# 02_-STLinkV2_1.net
KiCad netlist of a schematic drawn in Altium Designer
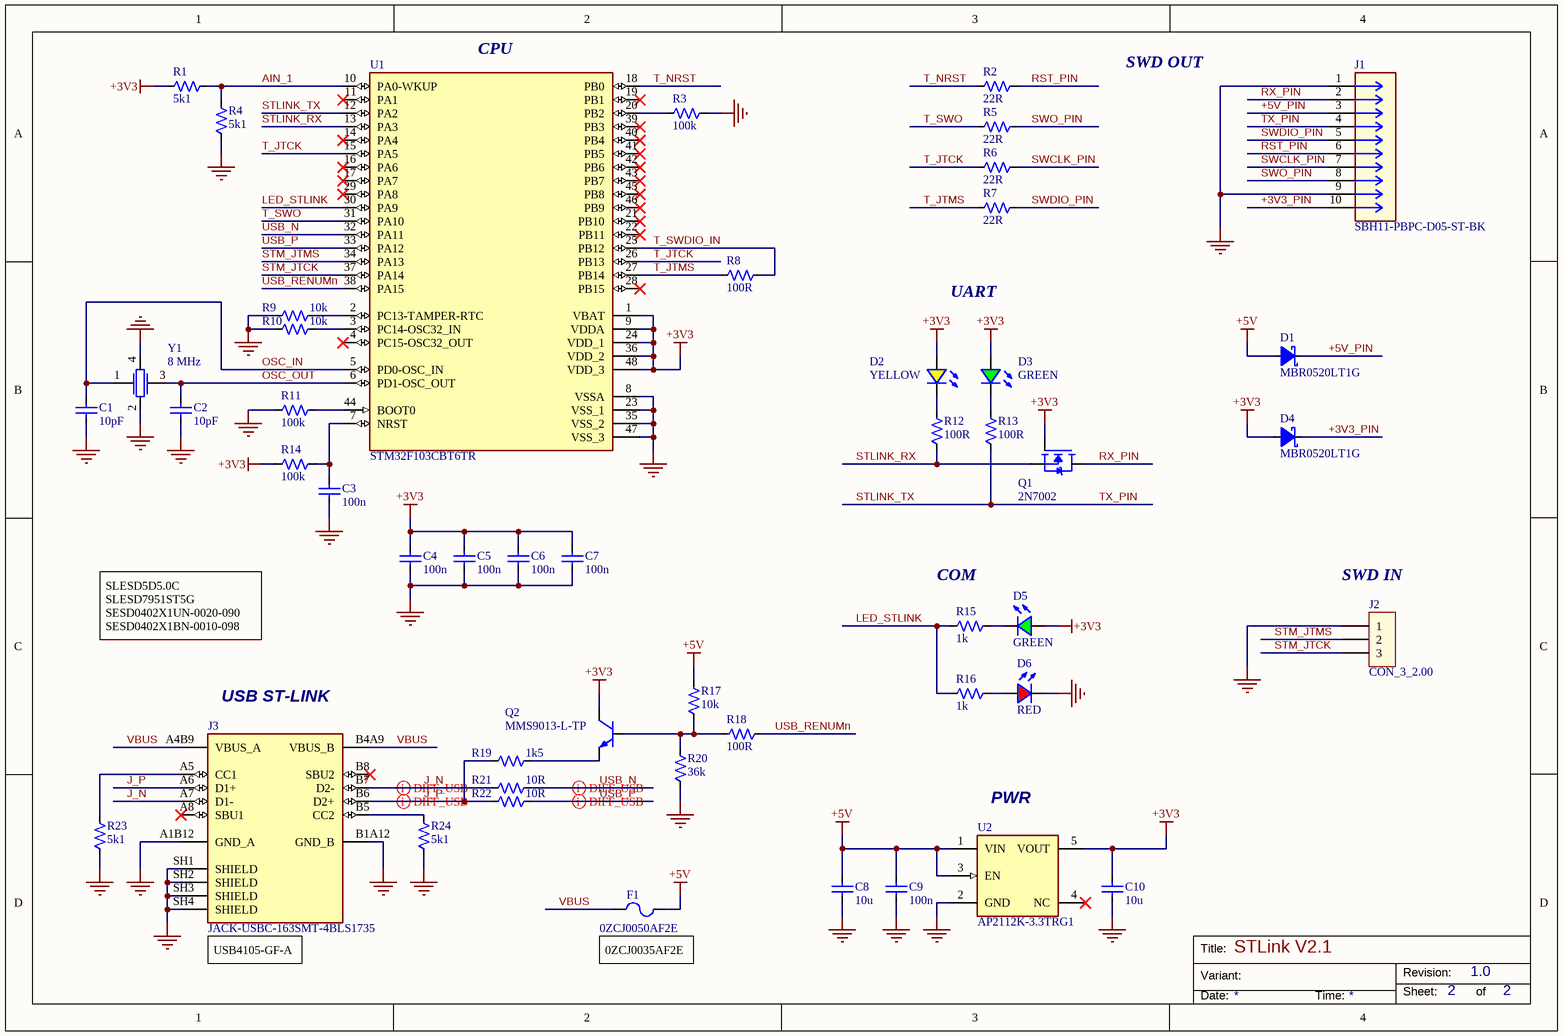
[diagram p0: [02]-STLinkV2_1.SchDoc]

(export (version "E")
  (design (tool "Eeschema 10.0.6"))
  (components
    (comp (ref "C1")
      (value "10pF")
      (footprint "CAPC1005X55N")
      (description "50V 10pF C0G ±5% 0402 Multilayer Ceramic Capacitors MLCC - SMD/SMT ROHS")
      (fields (field (name "TOLERANCE") "5%"))
      (libsource (lib "STLinkV2_1") (part "CAP_GCM1555C1H100JA16D"))
    )
    (comp (ref "C2")
      (value "10pF")
      (footprint "CAPC1005X55N")
      (description "50V 10pF C0G ±5% 0402 Multilayer Ceramic Capacitors MLCC - SMD/SMT ROHS")
      (fields (field (name "TOLERANCE") "5%"))
      (libsource (lib "STLinkV2_1") (part "CAP_GCM1555C1H100JA16D"))
    )
    (comp (ref "C3")
      (value "100n")
      (footprint "CAPC1005X55N")
      (description "50V 100nF X7R ±10% 0402 Multilayer Ceramic Capacitors MLCC - SMD/SMT ROHS")
      (fields (field (name "TOLERANCE") "10%"))
      (libsource (lib "STLinkV2_1") (part "CAP_GCM155R71H104KE02D"))
    )
    (comp (ref "C4")
      (value "100n")
      (footprint "CAPC1005X55N")
      (description "50V 100nF X7R ±10% 0402 Multilayer Ceramic Capacitors MLCC - SMD/SMT ROHS")
      (fields (field (name "TOLERANCE") "10%"))
      (libsource (lib "STLinkV2_1") (part "CAP_GCM155R71H104KE02D"))
    )
    (comp (ref "C5")
      (value "100n")
      (footprint "CAPC1005X55N")
      (description "50V 100nF X7R ±10% 0402 Multilayer Ceramic Capacitors MLCC - SMD/SMT ROHS")
      (fields (field (name "TOLERANCE") "10%"))
      (libsource (lib "STLinkV2_1") (part "CAP_GCM155R71H104KE02D"))
    )
    (comp (ref "C6")
      (value "100n")
      (footprint "CAPC1005X55N")
      (description "50V 100nF X7R ±10% 0402 Multilayer Ceramic Capacitors MLCC - SMD/SMT ROHS")
      (fields (field (name "TOLERANCE") "10%"))
      (libsource (lib "STLinkV2_1") (part "CAP_GCM155R71H104KE02D"))
    )
    (comp (ref "C7")
      (value "100n")
      (footprint "CAPC1005X55N")
      (description "50V 100nF X7R ±10% 0402 Multilayer Ceramic Capacitors MLCC - SMD/SMT ROHS")
      (fields (field (name "TOLERANCE") "10%"))
      (libsource (lib "STLinkV2_1") (part "CAP_GCM155R71H104KE02D"))
    )
    (comp (ref "C8")
      (value "10u")
      (footprint "CAPC0603(1608Metric)L")
      (description "CAP CER 10UF 6.3V X7R 0603")
      (fields (field (name "TOLERANCE") "20%") (field (name "MFG PART NUMBER") "GRM188C81C106MA73D"))
      (libsource (lib "STLinkV2_1") (part "GRM188C81C106MA73D"))
    )
    (comp (ref "C9")
      (value "100n")
      (footprint "CAPC1005X55N")
      (description "50V 100nF X7R ±10% 0402 Multilayer Ceramic Capacitors MLCC - SMD/SMT ROHS")
      (fields (field (name "TOLERANCE") "10%"))
      (libsource (lib "STLinkV2_1") (part "CAP_GCM155R71H104KE02D"))
    )
    (comp (ref "C10")
      (value "10u")
      (footprint "CAPC0603(1608Metric)L")
      (description "CAP CER 10UF 6.3V X7R 0603")
      (fields (field (name "TOLERANCE") "20%") (field (name "MFG PART NUMBER") "GRM188C81C106MA73D"))
      (libsource (lib "STLinkV2_1") (part "GRM188C81C106MA73D"))
    )
    (comp (ref "D1")
      (value "MBR0520LT1G")
      (footprint "SOD3716X135N")
      (description "Diode, Schottky Barrier, Vr 20V, If 0.5A, Pkg SOD-123, Vf 0.385V, Tj +125DEGC, Cs 5.5A")
      (libsource (lib "STLinkV2_1") (part "MBR0520LT1G"))
    )
    (comp (ref "D2")
      (value "YELLOW")
      (footprint "WL-SMCW_0603_150060xx75003")
      (description "Led, Yellow, 550Mcd, 595Nm Rohs Compliant: Yes")
      (libsource (lib "STLinkV2_1") (part "150060YS75003"))
    )
    (comp (ref "D3")
      (value "GREEN")
      (footprint "WL-SMCW_0603_150060xx75003")
      (description "Led, Bright Green, 100Mcd, 572Nm Rohs Compliant: Yes")
      (libsource (lib "STLinkV2_1") (part "150060VS75003"))
    )
    (comp (ref "D4")
      (value "MBR0520LT1G")
      (footprint "SOD3716X135N")
      (description "Diode, Schottky Barrier, Vr 20V, If 0.5A, Pkg SOD-123, Vf 0.385V, Tj +125DEGC, Cs 5.5A")
      (libsource (lib "STLinkV2_1") (part "MBR0520LT1G"))
    )
    (comp (ref "D5")
      (value "GREEN")
      (footprint "WL-SMCW_0603_150060xx75003")
      (description "Led, Bright Green, 100Mcd, 572Nm Rohs Compliant: Yes")
      (libsource (lib "STLinkV2_1") (part "150060VS75003"))
    )
    (comp (ref "D6")
      (value "RED")
      (description "SMT Mono-Color Chip LED Waterclear Advance WL-SMCW_0603_ADVANCE")
      (libsource (lib "STLinkV2_1") (part "150060RS75003"))
    )
    (comp (ref "F1")
      (value "0ZCJ0050AF2E")
      (footprint "0ZCJ_BEL")
      (description "Resettable Fuse, PPTC, 1206 (3216 Metric), 0ZCJ Series, 24 VDC, 500 mA, 1 A, 0.1 s")
      (libsource (lib "STLinkV2_1") (part "0ZCJ0050AF2E"))
    )
    (comp (ref "J1")
      (value "SBH11-PBPC-D05-ST-BK")
      (footprint "SULLINS_SBH11-PBPC-D05-ST-BK-H")
      (description "Conn Shrouded Header (4 Sides) HDR 10 POS 2.54mm Solder ST Top Entry Thru-Hole")
      (libsource (lib "STLinkV2_1") (part "SBH11-PBPC-D05-ST-BK"))
    )
    (comp (ref "J2")
      (value "CON_3_2.00")
      (footprint "Pin3")
      (libsource (lib "STLinkV2_1") (part "CON_3_2.00"))
    )
    (comp (ref "J3")
      (value "JACK-USBC-163SMT-4BLS1735")
      (footprint "JACK-USBC-163SMT-4BLS1735")
      (description "Usb Type C Jack IPX7 SMT")
      (libsource (lib "STLinkV2_1") (part "JACK-USBC-163SMT-4BLS1735"))
    )
    (comp (ref "Q1")
      (value "2N7002")
      (footprint "SOT23-3")
      (description "MOSFET N-CH 60V 300MA SOT23-3 N-Channel 60 V 300mA (Ta) 500mW (Ta) Surface Mount PG-SOT23")
      (libsource (lib "STLinkV2_1") (part "2N7002H6327XTSA2"))
    )
    (comp (ref "Q2")
      (value "MMS9013-L-TP")
      (footprint "SOT23-3")
      (description "Small Signal Bipolar Transistor, 0.5A I(C), 25V V(BR)CEO, 1-Element, NPN, Silicon")
      (libsource (lib "STLinkV2_1") (part "MMS9013-L-TP"))
    )
    (comp (ref "R1")
      (value "5k1")
      (footprint "RESC1005X37N")
      (description "Res Thick Film 0402 5.1K Ohm 1% 0.063W(1/16W) ±100ppm/°C Pad SMD T/R Automotive AEC-Q200")
      (fields (field (name "TOLERANCE") "1%"))
      (libsource (lib "STLinkV2_1") (part "RES_AC0402FR-135K1L"))
    )
    (comp (ref "R2")
      (value "22R")
      (footprint "RESC1005X37N")
      (description "125mW Thick Film Resistors ±100ppm/℃ ±1% 22Ω 0402 Chip Resistor - Surface Mount ROHS")
      (fields (field (name "TOLERANCE") "1%"))
      (libsource (lib "STLinkV2_1") (part "RES_AC0402FR-7W22RL"))
    )
    (comp (ref "R3")
      (value "100k")
      (footprint "RESC1005X37N")
      (description "Res Thick Film 0402 100K Ohm 1% 0.125W(1/8W) ±100ppm/°C Pad SMD T/R Automotive AEC-Q200")
      (fields (field (name "TOLERANCE") "1%"))
      (libsource (lib "STLinkV2_1") (part "RES_AC0402FR-7W100KL"))
    )
    (comp (ref "R4")
      (value "5k1")
      (footprint "RESC1005X37N")
      (description "Res Thick Film 0402 5.1K Ohm 1% 0.063W(1/16W) ±100ppm/°C Pad SMD T/R Automotive AEC-Q200")
      (fields (field (name "TOLERANCE") "1%"))
      (libsource (lib "STLinkV2_1") (part "RES_AC0402FR-135K1L"))
    )
    (comp (ref "R5")
      (value "22R")
      (footprint "RESC1005X37N")
      (description "125mW Thick Film Resistors ±100ppm/℃ ±1% 22Ω 0402 Chip Resistor - Surface Mount ROHS")
      (fields (field (name "TOLERANCE") "1%"))
      (libsource (lib "STLinkV2_1") (part "RES_AC0402FR-7W22RL"))
    )
    (comp (ref "R6")
      (value "22R")
      (footprint "RESC1005X37N")
      (description "125mW Thick Film Resistors ±100ppm/℃ ±1% 22Ω 0402 Chip Resistor - Surface Mount ROHS")
      (fields (field (name "TOLERANCE") "1%"))
      (libsource (lib "STLinkV2_1") (part "RES_AC0402FR-7W22RL"))
    )
    (comp (ref "R7")
      (value "22R")
      (footprint "RESC1005X37N")
      (description "125mW Thick Film Resistors ±100ppm/℃ ±1% 22Ω 0402 Chip Resistor - Surface Mount ROHS")
      (fields (field (name "TOLERANCE") "1%"))
      (libsource (lib "STLinkV2_1") (part "RES_AC0402FR-7W22RL"))
    )
    (comp (ref "R8")
      (value "100R")
      (footprint "RESC1005X37N")
      (description "Res Thick Film 0402 100 Ohm 1% 0.125W(1/8W) ±100ppm/C Pad SMD T/R Automotive AEC-Q200")
      (fields (field (name "TOLERANCE") "1%"))
      (libsource (lib "STLinkV2_1") (part "RES_AC0402FR-7W100RL"))
    )
    (comp (ref "R9")
      (value "10k")
      (footprint "RESC1005X37N")
      (description "Res Thick Film 0402 10K Ohm 1% 0.125W(1/8W) ±100ppm/C Pad SMD Automotive T/R")
      (fields (field (name "TOLERANCE") "1%"))
      (libsource (lib "STLinkV2_1") (part "RES_AC0402FR-7W10KL"))
    )
    (comp (ref "R10")
      (value "10k")
      (footprint "RESC1005X37N")
      (description "Res Thick Film 0402 10K Ohm 1% 0.125W(1/8W) ±100ppm/C Pad SMD Automotive T/R")
      (fields (field (name "TOLERANCE") "1%"))
      (libsource (lib "STLinkV2_1") (part "RES_AC0402FR-7W10KL"))
    )
    (comp (ref "R11")
      (value "100k")
      (footprint "RESC1005X37N")
      (description "Res Thick Film 0402 100K Ohm 1% 0.125W(1/8W) ±100ppm/°C Pad SMD T/R Automotive AEC-Q200")
      (fields (field (name "TOLERANCE") "1%"))
      (libsource (lib "STLinkV2_1") (part "RES_AC0402FR-7W100KL"))
    )
    (comp (ref "R12")
      (value "100R")
      (footprint "RESC1005X37N")
      (description "Res Thick Film 0402 100 Ohm 1% 0.125W(1/8W) ±100ppm/C Pad SMD T/R Automotive AEC-Q200")
      (fields (field (name "TOLERANCE") "1%"))
      (libsource (lib "STLinkV2_1") (part "RES_AC0402FR-7W100RL"))
    )
    (comp (ref "R13")
      (value "100R")
      (footprint "RESC1005X37N")
      (description "Res Thick Film 0402 100 Ohm 1% 0.125W(1/8W) ±100ppm/C Pad SMD T/R Automotive AEC-Q200")
      (fields (field (name "TOLERANCE") "1%"))
      (libsource (lib "STLinkV2_1") (part "RES_AC0402FR-7W100RL"))
    )
    (comp (ref "R14")
      (value "100k")
      (footprint "RESC1005X37N")
      (description "Res Thick Film 0402 100K Ohm 1% 0.125W(1/8W) ±100ppm/°C Pad SMD T/R Automotive AEC-Q200")
      (fields (field (name "TOLERANCE") "1%"))
      (libsource (lib "STLinkV2_1") (part "RES_AC0402FR-7W100KL"))
    )
    (comp (ref "R15")
      (value "1k")
      (footprint "RESC1005X37N")
      (description "Res Thick Film 0402 1K Ohm 1% 0.125W(1/8W) ±100ppm/C Pad SMD Automotive T/R")
      (fields (field (name "TOLERANCE") "1%"))
      (libsource (lib "STLinkV2_1") (part "RES_AC0402FR-7W1KL"))
    )
    (comp (ref "R16")
      (value "1k")
      (footprint "RESC1005X37N")
      (description "Res Thick Film 0402 1K Ohm 1% 0.125W(1/8W) ±100ppm/C Pad SMD Automotive T/R")
      (fields (field (name "TOLERANCE") "1%"))
      (libsource (lib "STLinkV2_1") (part "RES_AC0402FR-7W1KL"))
    )
    (comp (ref "R17")
      (value "10k")
      (footprint "RESC1005X37N")
      (description "Res Thick Film 0402 10K Ohm 1% 0.125W(1/8W) ±100ppm/C Pad SMD Automotive T/R")
      (fields (field (name "TOLERANCE") "1%"))
      (libsource (lib "STLinkV2_1") (part "RES_AC0402FR-7W10KL"))
    )
    (comp (ref "R18")
      (value "100R")
      (footprint "RESC1005X37N")
      (description "Res Thick Film 0402 100 Ohm 1% 0.125W(1/8W) ±100ppm/C Pad SMD T/R Automotive AEC-Q200")
      (fields (field (name "TOLERANCE") "1%"))
      (libsource (lib "STLinkV2_1") (part "RES_AC0402FR-7W100RL"))
    )
    (comp (ref "R19")
      (value "1k5")
      (footprint "RESC1005X37N")
      (fields (field (name "TOLERANCE") "1%"))
      (libsource (lib "STLinkV2_1") (part "RES_AC0402FR-7W1K5L"))
    )
    (comp (ref "R20")
      (value "36k")
      (footprint "RESC1005X37N")
      (description "Chip Resistor Automotive Grade Thick Film 0402 36kOhm 1% Paper T/R")
      (fields (field (name "TOLERANCE") "1%"))
      (libsource (lib "STLinkV2_1") (part "RES_AC0402FR-7W36KL"))
    )
    (comp (ref "R21")
      (value "10R")
      (footprint "RESC1005X37N")
      (description "Res Thick Film 0402 10 Ohm 1% 0.125W(1/8W) ±100ppm/C Pad SMD T/R Automotive AEC-Q200")
      (fields (field (name "TOLERANCE") "1%"))
      (libsource (lib "STLinkV2_1") (part "RES_AC0402FR-7W10RL"))
    )
    (comp (ref "R22")
      (value "10R")
      (footprint "RESC1005X37N")
      (description "Res Thick Film 0402 10 Ohm 1% 0.125W(1/8W) ±100ppm/C Pad SMD T/R Automotive AEC-Q200")
      (fields (field (name "TOLERANCE") "1%"))
      (libsource (lib "STLinkV2_1") (part "RES_AC0402FR-7W10RL"))
    )
    (comp (ref "R23")
      (value "5k1")
      (footprint "RESC1005X37N")
      (description "Res Thick Film 0402 5.1K Ohm 1% 0.063W(1/16W) ±100ppm/°C Pad SMD T/R Automotive AEC-Q200")
      (fields (field (name "TOLERANCE") "1%"))
      (libsource (lib "STLinkV2_1") (part "RES_AC0402FR-135K1L"))
    )
    (comp (ref "R24")
      (value "5k1")
      (footprint "RESC1005X37N")
      (description "Res Thick Film 0402 5.1K Ohm 1% 0.063W(1/16W) ±100ppm/°C Pad SMD T/R Automotive AEC-Q200")
      (fields (field (name "TOLERANCE") "1%"))
      (libsource (lib "STLinkV2_1") (part "RES_AC0402FR-135K1L"))
    )
    (comp (ref "U1")
      (value "STM32F103CBT6TR")
      (footprint "QFP50P900X900X160-48N")
      (description "MCU 32-bit STM32F1 ARM Cortex M3 RISC 128KB Flash 2.5V/3.3V 48-Pin LQFP T/R")
      (libsource (lib "STLinkV2_1") (part "STM32F103CBT6TR"))
    )
    (comp (ref "U2")
      (value "AP2112K-3.3TRG1")
      (footprint "SOT95P285X140-5N")
      (description "AP2112 Series 0.6 A 3.3 V Fixed Output SMT LDO Linear Regulator - SOT23-5")
      (libsource (lib "STLinkV2_1") (part "AP2112K-3.3TRG1"))
    )
    (comp (ref "Y1")
      (value "8 MHz")
      (footprint "XTAL_C3E-8.000-8-1015-R")
      (description "CRYSTAL 8.0000MHZ 10PF SMD")
      (fields (field (name "MFG") "ECS Inc.") (field (name "MFG PART NUMBER") "ECS-80-10-33-CKM-TR3"))
      (libsource (lib "STLinkV2_1") (part "Y_ECS-80-10-33-CKM-TR3"))
    )
  )
  (nets
    (net (code "1") (name "+3V3") (class "Default")
      (node (ref "C10") (pin "2") (pinfunction "2_2") (pintype "passive"))
      (node (ref "C4") (pin "1") (pinfunction "1_1") (pintype "passive"))
      (node (ref "C5") (pin "1") (pinfunction "1_1") (pintype "passive"))
      (node (ref "C6") (pin "1") (pinfunction "1_1") (pintype "passive"))
      (node (ref "C7") (pin "1") (pinfunction "1_1") (pintype "passive"))
      (node (ref "D2") (pin "1") (pinfunction "POS_1") (pintype "passive"))
      (node (ref "D3") (pin "1") (pinfunction "POS_1") (pintype "passive"))
      (node (ref "D4") (pin "1") (pinfunction "A_1") (pintype "passive"))
      (node (ref "D5") (pin "1") (pinfunction "POS_1") (pintype "passive"))
      (node (ref "Q1") (pin "1") (pinfunction "G_1") (pintype "passive"))
      (node (ref "Q2") (pin "3") (pinfunction "C_3") (pintype "passive"))
      (node (ref "R1") (pin "2") (pinfunction "2_2") (pintype "passive"))
      (node (ref "R14") (pin "2") (pinfunction "2_2") (pintype "passive"))
      (node (ref "U1") (pin "1") (pinfunction "VBAT_1") (pintype "power_in"))
      (node (ref "U1") (pin "24") (pinfunction "VDD_1_24") (pintype "power_in"))
      (node (ref "U1") (pin "36") (pinfunction "VDD_2_36") (pintype "power_in"))
      (node (ref "U1") (pin "48") (pinfunction "VDD_3_48") (pintype "power_in"))
      (node (ref "U1") (pin "9") (pinfunction "VDDA_9") (pintype "power_in"))
      (node (ref "U2") (pin "5") (pinfunction "VOUT_5") (pintype "power_in"))
    )
    (net (code "2") (name "+5V") (class "Default")
      (node (ref "C8") (pin "2") (pinfunction "2_2") (pintype "passive"))
      (node (ref "C9") (pin "1") (pinfunction "1_1") (pintype "passive"))
      (node (ref "D1") (pin "1") (pinfunction "A_1") (pintype "passive"))
      (node (ref "F1") (pin "2") (pinfunction "2_2") (pintype "passive"))
      (node (ref "R17") (pin "1") (pinfunction "1_1") (pintype "passive"))
      (node (ref "U2") (pin "1") (pinfunction "VIN_1") (pintype "power_in"))
      (node (ref "U2") (pin "3") (pinfunction "EN_3") (pintype "input"))
    )
    (net (code "3") (name "/+3V3_PIN") (class "Default")
      (node (ref "D4") (pin "2") (pinfunction "K_2") (pintype "passive"))
      (node (ref "J1") (pin "10") (pinfunction "10_10") (pintype "passive"))
    )
    (net (code "4") (name "/+5V_PIN") (class "Default")
      (node (ref "D1") (pin "2") (pinfunction "K_2") (pintype "passive"))
      (node (ref "J1") (pin "3") (pinfunction "3_3") (pintype "passive"))
    )
    (net (code "5") (name "/AIN_1") (class "Default")
      (node (ref "R1") (pin "1") (pinfunction "1_1") (pintype "passive"))
      (node (ref "R4") (pin "1") (pinfunction "1_1") (pintype "passive"))
      (node (ref "U1") (pin "10") (pinfunction "PA0-WKUP_10") (pintype "bidirectional"))
    )
    (net (code "6") (name "/J_N") (class "Default")
      (node (ref "J3") (pin "A7") (pinfunction "D1-_A7") (pintype "bidirectional"))
      (node (ref "J3") (pin "B7") (pinfunction "D2-_B7") (pintype "bidirectional"))
      (node (ref "R21") (pin "2") (pinfunction "2_2") (pintype "passive"))
    )
    (net (code "7") (name "/J_P") (class "Default")
      (node (ref "J3") (pin "A6") (pinfunction "D1+_A6") (pintype "bidirectional"))
      (node (ref "J3") (pin "B6") (pinfunction "D2+_B6") (pintype "bidirectional"))
      (node (ref "R19") (pin "2") (pinfunction "2_2") (pintype "passive"))
      (node (ref "R22") (pin "2") (pinfunction "2_2") (pintype "passive"))
    )
    (net (code "8") (name "/LED_STLINK") (class "Default")
      (node (ref "R15") (pin "2") (pinfunction "2_2") (pintype "passive"))
      (node (ref "R16") (pin "2") (pinfunction "2_2") (pintype "passive"))
      (node (ref "U1") (pin "30") (pinfunction "PA9_30") (pintype "bidirectional"))
    )
    (net (code "9") (name "/OSC_IN") (class "Default")
      (node (ref "C1") (pin "2") (pinfunction "2_2") (pintype "passive"))
      (node (ref "U1") (pin "5") (pinfunction "PD0-OSC_IN_5") (pintype "bidirectional"))
      (node (ref "Y1") (pin "1") (pinfunction "1_1") (pintype "passive"))
    )
    (net (code "10") (name "/OSC_OUT") (class "Default")
      (node (ref "C2") (pin "2") (pinfunction "2_2") (pintype "passive"))
      (node (ref "U1") (pin "6") (pinfunction "PD1-OSC_OUT_6") (pintype "bidirectional"))
      (node (ref "Y1") (pin "3") (pinfunction "2_3") (pintype "passive"))
    )
    (net (code "11") (name "/RST_PIN") (class "Default")
      (node (ref "J1") (pin "6") (pinfunction "6_6") (pintype "passive"))
      (node (ref "R2") (pin "1") (pinfunction "1_1") (pintype "passive"))
    )
    (net (code "12") (name "/RX_PIN") (class "Default")
      (node (ref "J1") (pin "2") (pinfunction "2_2") (pintype "passive"))
      (node (ref "Q1") (pin "3") (pinfunction "D_3") (pintype "passive"))
    )
    (net (code "13") (name "/STLINK_RX") (class "Default")
      (node (ref "Q1") (pin "2") (pinfunction "S_2") (pintype "passive"))
      (node (ref "R12") (pin "2") (pinfunction "2_2") (pintype "passive"))
      (node (ref "U1") (pin "13") (pinfunction "PA3_13") (pintype "bidirectional"))
    )
    (net (code "14") (name "/STLINK_TX") (class "Default")
      (node (ref "J1") (pin "4") (pinfunction "4_4") (pintype "passive"))
      (node (ref "R13") (pin "2") (pinfunction "2_2") (pintype "passive"))
      (node (ref "U1") (pin "12") (pinfunction "PA2_12") (pintype "bidirectional"))
    )
    (net (code "15") (name "/STM_JTCK") (class "Default")
      (node (ref "J2") (pin "3") (pinfunction "3_3") (pintype "passive"))
      (node (ref "U1") (pin "37") (pinfunction "PA14_37") (pintype "bidirectional"))
    )
    (net (code "16") (name "/STM_JTMS") (class "Default")
      (node (ref "J2") (pin "2") (pinfunction "2_2") (pintype "passive"))
      (node (ref "U1") (pin "34") (pinfunction "PA13_34") (pintype "bidirectional"))
    )
    (net (code "17") (name "/SWCLK_PIN") (class "Default")
      (node (ref "J1") (pin "7") (pinfunction "7_7") (pintype "passive"))
      (node (ref "R6") (pin "1") (pinfunction "1_1") (pintype "passive"))
    )
    (net (code "18") (name "/SWDIO_PIN") (class "Default")
      (node (ref "J1") (pin "5") (pinfunction "5_5") (pintype "passive"))
      (node (ref "R7") (pin "1") (pinfunction "1_1") (pintype "passive"))
    )
    (net (code "19") (name "/SWO_PIN") (class "Default")
      (node (ref "J1") (pin "8") (pinfunction "8_8") (pintype "passive"))
      (node (ref "R5") (pin "1") (pinfunction "1_1") (pintype "passive"))
    )
    (net (code "20") (name "/T_JTCK") (class "Default")
      (node (ref "R6") (pin "2") (pinfunction "2_2") (pintype "passive"))
      (node (ref "U1") (pin "15") (pinfunction "PA5_15") (pintype "bidirectional"))
      (node (ref "U1") (pin "26") (pinfunction "PB13_26") (pintype "bidirectional"))
    )
    (net (code "21") (name "/T_JTMS") (class "Default")
      (node (ref "R7") (pin "2") (pinfunction "2_2") (pintype "passive"))
      (node (ref "R8") (pin "2") (pinfunction "2_2") (pintype "passive"))
      (node (ref "U1") (pin "27") (pinfunction "PB14_27") (pintype "bidirectional"))
    )
    (net (code "22") (name "/T_NRST") (class "Default")
      (node (ref "R2") (pin "2") (pinfunction "2_2") (pintype "passive"))
      (node (ref "U1") (pin "18") (pinfunction "PB0_18") (pintype "bidirectional"))
    )
    (net (code "23") (name "/T_SWDIO_IN") (class "Default")
      (node (ref "R8") (pin "1") (pinfunction "1_1") (pintype "passive"))
      (node (ref "U1") (pin "25") (pinfunction "PB12_25") (pintype "bidirectional"))
    )
    (net (code "24") (name "/T_SWO") (class "Default")
      (node (ref "R5") (pin "2") (pinfunction "2_2") (pintype "passive"))
      (node (ref "U1") (pin "31") (pinfunction "PA10_31") (pintype "bidirectional"))
    )
    (net (code "25") (name "/USB_N") (class "Default")
      (node (ref "R21") (pin "1") (pinfunction "1_1") (pintype "passive"))
      (node (ref "U1") (pin "32") (pinfunction "PA11_32") (pintype "bidirectional"))
    )
    (net (code "26") (name "/USB_P") (class "Default")
      (node (ref "R22") (pin "1") (pinfunction "1_1") (pintype "passive"))
      (node (ref "U1") (pin "33") (pinfunction "PA12_33") (pintype "bidirectional"))
    )
    (net (code "27") (name "/USB_RENUMn") (class "Default")
      (node (ref "R18") (pin "2") (pinfunction "2_2") (pintype "passive"))
      (node (ref "U1") (pin "38") (pinfunction "PA15_38") (pintype "bidirectional"))
    )
    (net (code "28") (name "/VBUS") (class "Default")
      (node (ref "F1") (pin "1") (pinfunction "1_1") (pintype "passive"))
      (node (ref "J3") (pin "A4B9") (pinfunction "VBUS_A_A4B9") (pintype "power_in"))
      (node (ref "J3") (pin "B4A9") (pinfunction "VBUS_B_B4A9") (pintype "power_in"))
    )
    (net (code "29") (name "GND") (class "Default")
      (node (ref "C1") (pin "1") (pinfunction "1_1") (pintype "passive"))
      (node (ref "C10") (pin "1") (pinfunction "1_1") (pintype "passive"))
      (node (ref "C2") (pin "1") (pinfunction "1_1") (pintype "passive"))
      (node (ref "C3") (pin "2") (pinfunction "2_2") (pintype "passive"))
      (node (ref "C4") (pin "2") (pinfunction "2_2") (pintype "passive"))
      (node (ref "C5") (pin "2") (pinfunction "2_2") (pintype "passive"))
      (node (ref "C6") (pin "2") (pinfunction "2_2") (pintype "passive"))
      (node (ref "C7") (pin "2") (pinfunction "2_2") (pintype "passive"))
      (node (ref "C8") (pin "1") (pinfunction "1_1") (pintype "passive"))
      (node (ref "C9") (pin "2") (pinfunction "2_2") (pintype "passive"))
      (node (ref "D6") (pin "2") (pinfunction "NEG_2") (pintype "passive"))
      (node (ref "J1") (pin "1") (pinfunction "1_1") (pintype "passive"))
      (node (ref "J1") (pin "9") (pinfunction "9_9") (pintype "passive"))
      (node (ref "J2") (pin "1") (pinfunction "1_1") (pintype "passive"))
      (node (ref "J3") (pin "A1B12") (pinfunction "GND_A_A1B12") (pintype "power_in"))
      (node (ref "J3") (pin "B1A12") (pinfunction "GND_B_B1A12") (pintype "power_in"))
      (node (ref "J3") (pin "SH1") (pinfunction "SHIELD_SH1") (pintype "passive"))
      (node (ref "J3") (pin "SH2") (pinfunction "SHIELD_SH2") (pintype "passive"))
      (node (ref "J3") (pin "SH3") (pinfunction "SHIELD_SH3") (pintype "passive"))
      (node (ref "J3") (pin "SH4") (pinfunction "SHIELD_SH4") (pintype "passive"))
      (node (ref "R10") (pin "2") (pinfunction "2_2") (pintype "passive"))
      (node (ref "R11") (pin "2") (pinfunction "2_2") (pintype "passive"))
      (node (ref "R20") (pin "2") (pinfunction "2_2") (pintype "passive"))
      (node (ref "R23") (pin "2") (pinfunction "2_2") (pintype "passive"))
      (node (ref "R24") (pin "2") (pinfunction "2_2") (pintype "passive"))
      (node (ref "R3") (pin "1") (pinfunction "1_1") (pintype "passive"))
      (node (ref "R4") (pin "2") (pinfunction "2_2") (pintype "passive"))
      (node (ref "R9") (pin "2") (pinfunction "2_2") (pintype "passive"))
      (node (ref "U1") (pin "23") (pinfunction "VSS_1_23") (pintype "power_in"))
      (node (ref "U1") (pin "35") (pinfunction "VSS_2_35") (pintype "power_in"))
      (node (ref "U1") (pin "47") (pinfunction "VSS_3_47") (pintype "power_in"))
      (node (ref "U1") (pin "8") (pinfunction "VSSA_8") (pintype "power_in"))
      (node (ref "U2") (pin "2") (pinfunction "GND_2") (pintype "power_in"))
      (node (ref "Y1") (pin "2") (pinfunction "GND_2") (pintype "power_in"))
      (node (ref "Y1") (pin "4") (pinfunction "GND_4") (pintype "power_in"))
    )
    (net (code "30") (name "Net-(D2-NEG)") (class "Default")
      (node (ref "D2") (pin "2") (pinfunction "NEG_2") (pintype "passive"))
      (node (ref "R12") (pin "1") (pinfunction "1_1") (pintype "passive"))
    )
    (net (code "31") (name "Net-(D3-NEG)") (class "Default")
      (node (ref "D3") (pin "2") (pinfunction "NEG_2") (pintype "passive"))
      (node (ref "R13") (pin "1") (pinfunction "1_1") (pintype "passive"))
    )
    (net (code "32") (name "Net-(D5-NEG)") (class "Default")
      (node (ref "D5") (pin "2") (pinfunction "NEG_2") (pintype "passive"))
      (node (ref "R15") (pin "1") (pinfunction "1_1") (pintype "passive"))
    )
    (net (code "33") (name "Net-(D6-POS)") (class "Default")
      (node (ref "D6") (pin "1") (pinfunction "POS_1") (pintype "passive"))
      (node (ref "R16") (pin "1") (pinfunction "1_1") (pintype "passive"))
    )
    (net (code "34") (name "Net-(J3-CC1)") (class "Default")
      (node (ref "J3") (pin "A5") (pinfunction "CC1_A5") (pintype "bidirectional"))
      (node (ref "R23") (pin "1") (pinfunction "1_1") (pintype "passive"))
    )
    (net (code "35") (name "Net-(J3-CC2)") (class "Default")
      (node (ref "J3") (pin "B5") (pinfunction "CC2_B5") (pintype "bidirectional"))
      (node (ref "R24") (pin "1") (pinfunction "1_1") (pintype "passive"))
    )
    (net (code "36") (name "Net-(Q2-B)") (class "Default")
      (node (ref "Q2") (pin "1") (pinfunction "B_1") (pintype "passive"))
      (node (ref "R17") (pin "2") (pinfunction "2_2") (pintype "passive"))
      (node (ref "R18") (pin "1") (pinfunction "1_1") (pintype "passive"))
      (node (ref "R20") (pin "1") (pinfunction "1_1") (pintype "passive"))
    )
    (net (code "37") (name "Net-(Q2-E)") (class "Default")
      (node (ref "Q2") (pin "2") (pinfunction "E_2") (pintype "passive"))
      (node (ref "R19") (pin "1") (pinfunction "1_1") (pintype "passive"))
    )
    (net (code "38") (name "Net-(U1-BOOT0)") (class "Default")
      (node (ref "R11") (pin "1") (pinfunction "1_1") (pintype "passive"))
      (node (ref "U1") (pin "44") (pinfunction "BOOT0_44") (pintype "input"))
    )
    (net (code "39") (name "Net-(U1-NRST)") (class "Default")
      (node (ref "C3") (pin "1") (pinfunction "1_1") (pintype "passive"))
      (node (ref "R14") (pin "1") (pinfunction "1_1") (pintype "passive"))
      (node (ref "U1") (pin "7") (pinfunction "NRST_7") (pintype "bidirectional"))
    )
    (net (code "40") (name "Net-(U1-PB2)") (class "Default")
      (node (ref "R3") (pin "2") (pinfunction "2_2") (pintype "passive"))
      (node (ref "U1") (pin "20") (pinfunction "PB2_20") (pintype "bidirectional"))
    )
    (net (code "41") (name "Net-(U1-PC13-TAMPER-RTC)") (class "Default")
      (node (ref "R9") (pin "1") (pinfunction "1_1") (pintype "passive"))
      (node (ref "U1") (pin "2") (pinfunction "PC13-TAMPER-RTC_2") (pintype "bidirectional"))
    )
    (net (code "42") (name "Net-(U1-PC14-OSC32_IN)") (class "Default")
      (node (ref "R10") (pin "1") (pinfunction "1_1") (pintype "passive"))
      (node (ref "U1") (pin "3") (pinfunction "PC14-OSC32_IN_3") (pintype "bidirectional"))
    )
    (net (code "43") (name "unconnected-(J3-SBU1-PadA8)") (class "Default")
      (node (ref "J3") (pin "A8") (pinfunction "SBU1_A8") (pintype "bidirectional+no_connect"))
    )
    (net (code "44") (name "unconnected-(J3-SBU2-PadB8)") (class "Default")
      (node (ref "J3") (pin "B8") (pinfunction "SBU2_B8") (pintype "bidirectional+no_connect"))
    )
    (net (code "45") (name "unconnected-(U1-PA1-Pad11)") (class "Default")
      (node (ref "U1") (pin "11") (pinfunction "PA1_11") (pintype "bidirectional+no_connect"))
    )
    (net (code "46") (name "unconnected-(U1-PA4-Pad14)") (class "Default")
      (node (ref "U1") (pin "14") (pinfunction "PA4_14") (pintype "bidirectional+no_connect"))
    )
    (net (code "47") (name "unconnected-(U1-PA6-Pad16)") (class "Default")
      (node (ref "U1") (pin "16") (pinfunction "PA6_16") (pintype "bidirectional+no_connect"))
    )
    (net (code "48") (name "unconnected-(U1-PA7-Pad17)") (class "Default")
      (node (ref "U1") (pin "17") (pinfunction "PA7_17") (pintype "bidirectional+no_connect"))
    )
    (net (code "49") (name "unconnected-(U1-PA8-Pad29)") (class "Default")
      (node (ref "U1") (pin "29") (pinfunction "PA8_29") (pintype "bidirectional+no_connect"))
    )
    (net (code "50") (name "unconnected-(U1-PB1-Pad19)") (class "Default")
      (node (ref "U1") (pin "19") (pinfunction "PB1_19") (pintype "bidirectional+no_connect"))
    )
    (net (code "51") (name "unconnected-(U1-PB3-Pad39)") (class "Default")
      (node (ref "U1") (pin "39") (pinfunction "PB3_39") (pintype "bidirectional+no_connect"))
    )
    (net (code "52") (name "unconnected-(U1-PB4-Pad40)") (class "Default")
      (node (ref "U1") (pin "40") (pinfunction "PB4_40") (pintype "bidirectional+no_connect"))
    )
    (net (code "53") (name "unconnected-(U1-PB5-Pad41)") (class "Default")
      (node (ref "U1") (pin "41") (pinfunction "PB5_41") (pintype "bidirectional+no_connect"))
    )
    (net (code "54") (name "unconnected-(U1-PB6-Pad42)") (class "Default")
      (node (ref "U1") (pin "42") (pinfunction "PB6_42") (pintype "bidirectional+no_connect"))
    )
    (net (code "55") (name "unconnected-(U1-PB7-Pad43)") (class "Default")
      (node (ref "U1") (pin "43") (pinfunction "PB7_43") (pintype "bidirectional+no_connect"))
    )
    (net (code "56") (name "unconnected-(U1-PB8-Pad45)") (class "Default")
      (node (ref "U1") (pin "45") (pinfunction "PB8_45") (pintype "bidirectional+no_connect"))
    )
    (net (code "57") (name "unconnected-(U1-PB9-Pad46)") (class "Default")
      (node (ref "U1") (pin "46") (pinfunction "PB9_46") (pintype "bidirectional+no_connect"))
    )
    (net (code "58") (name "unconnected-(U1-PB10-Pad21)") (class "Default")
      (node (ref "U1") (pin "21") (pinfunction "PB10_21") (pintype "bidirectional+no_connect"))
    )
    (net (code "59") (name "unconnected-(U1-PB11-Pad22)") (class "Default")
      (node (ref "U1") (pin "22") (pinfunction "PB11_22") (pintype "bidirectional+no_connect"))
    )
    (net (code "60") (name "unconnected-(U1-PB15-Pad28)") (class "Default")
      (node (ref "U1") (pin "28") (pinfunction "PB15_28") (pintype "bidirectional+no_connect"))
    )
    (net (code "61") (name "unconnected-(U1-PC15-OSC32_OUT-Pad4)") (class "Default")
      (node (ref "U1") (pin "4") (pinfunction "PC15-OSC32_OUT_4") (pintype "bidirectional+no_connect"))
    )
    (net (code "62") (name "unconnected-(U2-NC-Pad4)") (class "Default")
      (node (ref "U2") (pin "4") (pinfunction "NC_4") (pintype "passive+no_connect"))
    )
  )
)
